# Connectors_GPIOs_old.net
KiCad netlist of a schematic drawn in Altium Designer
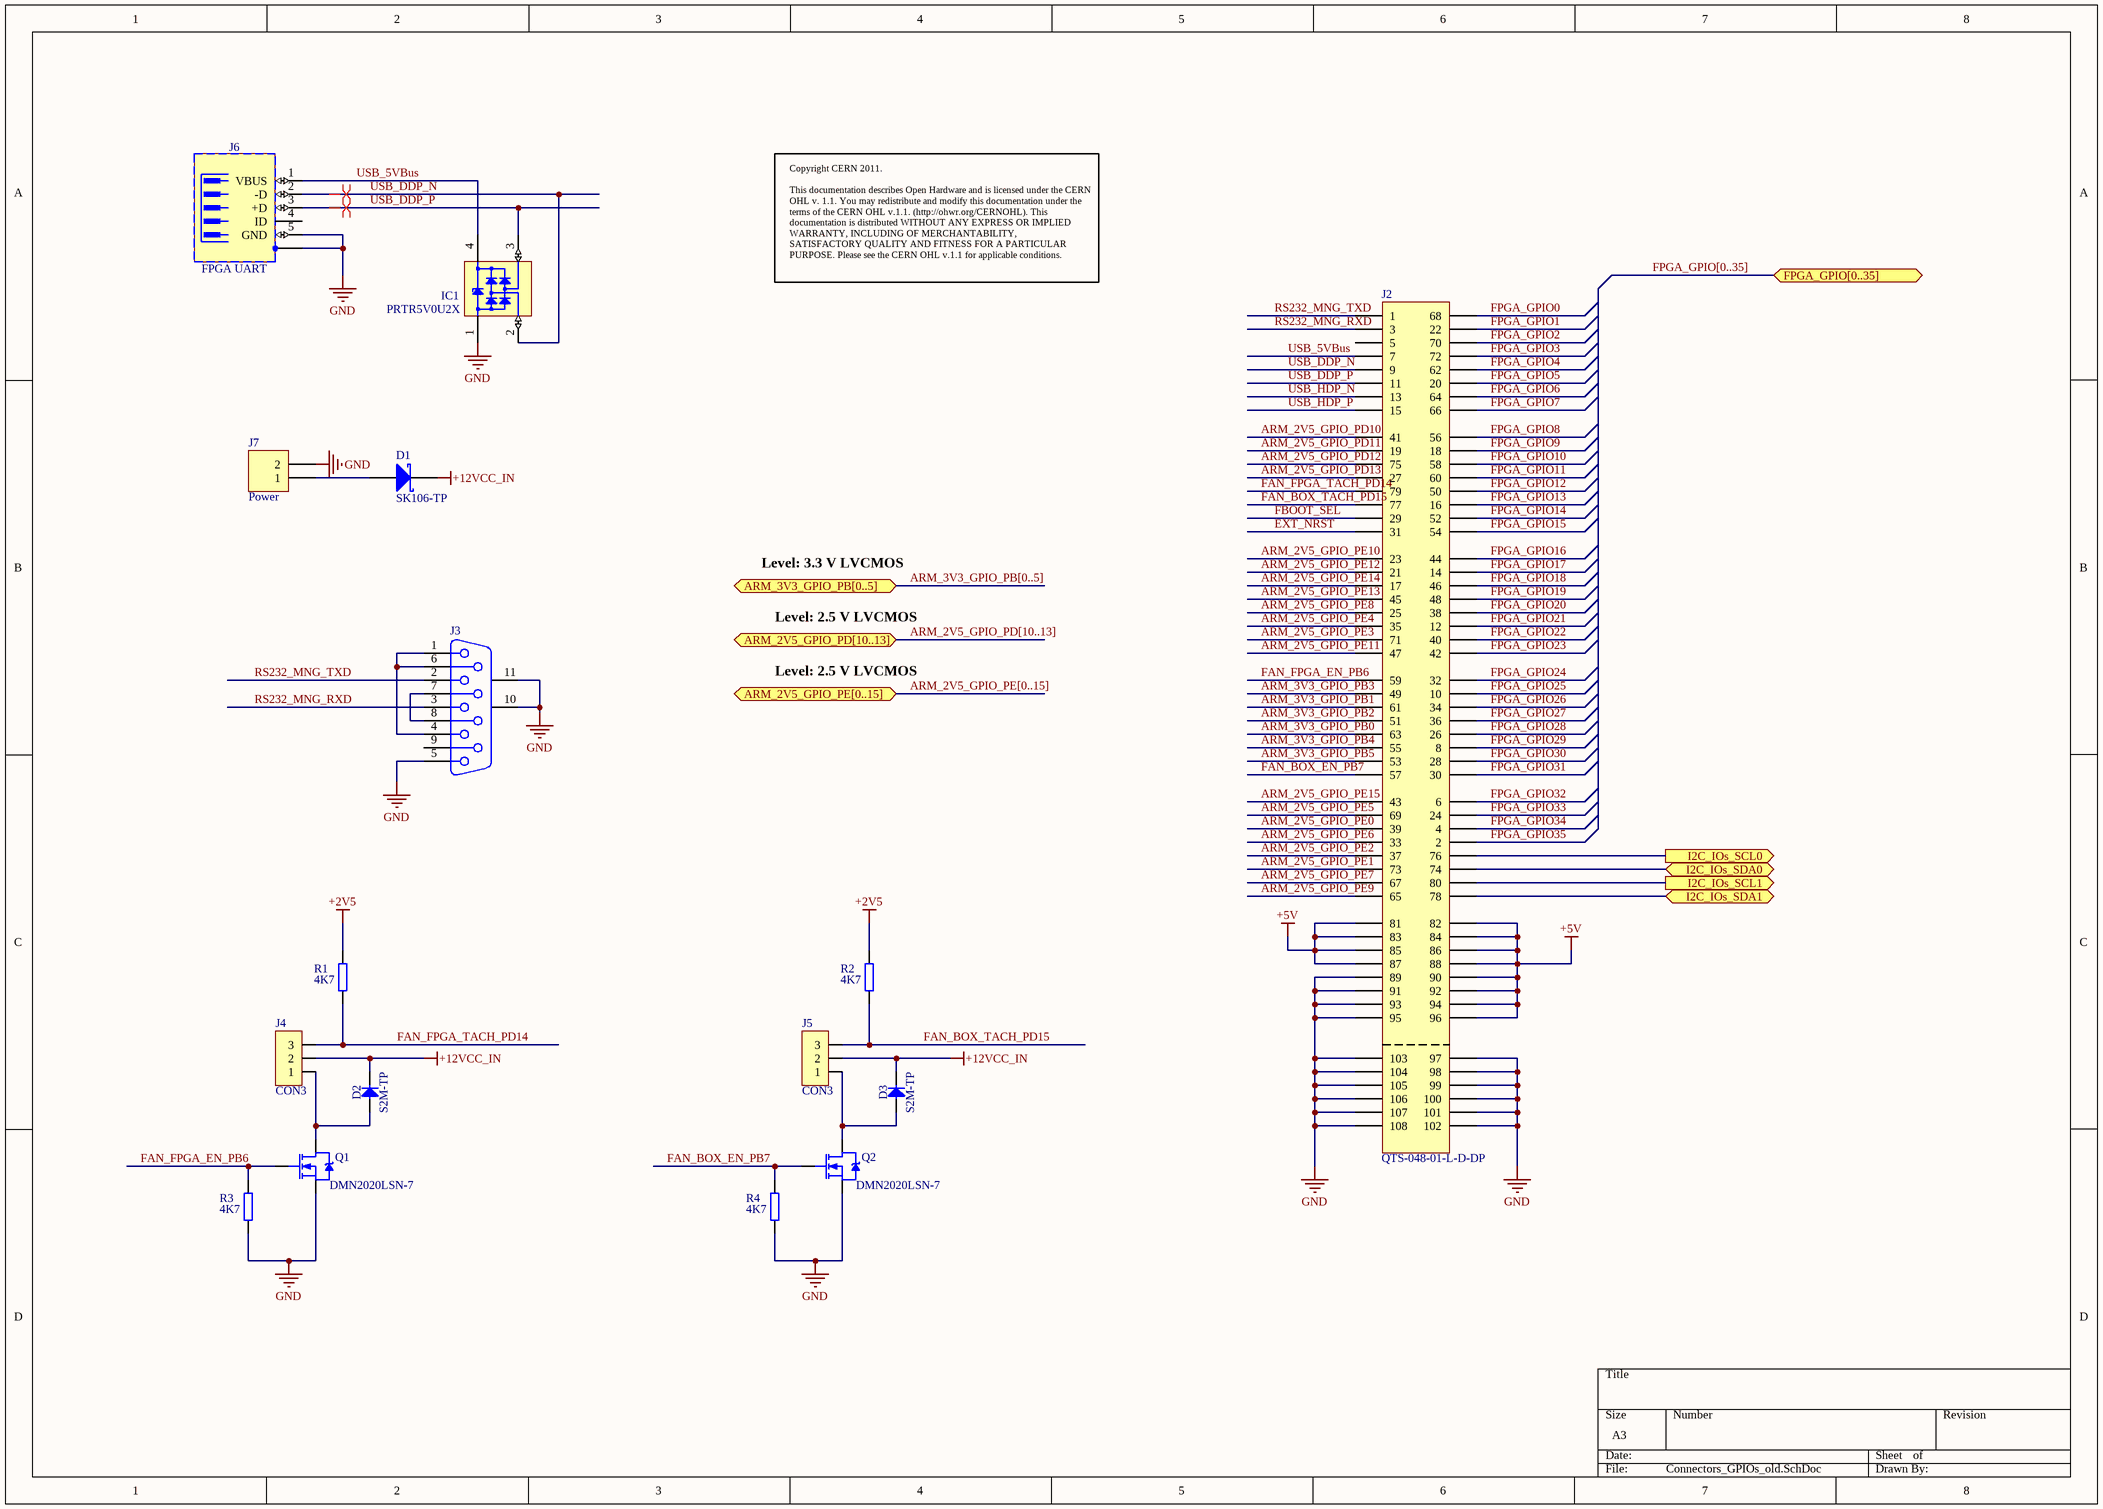
[diagram p0: Connectors_GPIOs_old.SchDoc]

(export (version "E")
  (design (tool "Eeschema 10.0.6"))
  (components
    (comp (ref "D1")
      (value "SK106-TP")
      (footprint "7S_WR:DO-214AB/SMB-MCC")
      (description "Schottky Diode 10A 60V")
      (libsource (lib "wr_switch") (part "SK106-TP"))
    )
    (comp (ref "D2")
      (value "S2M-TP")
      (footprint "DO-214AA/SMB-MCC")
      (description "2 A Silicon Rectifier 50 to 1000 Volts")
      (fields (field (name "AUTHOR") "CERN DEM JLC"))
      (libsource (lib "wr_switch") (part "S2M-TP"))
    )
    (comp (ref "D3")
      (value "S2M-TP")
      (footprint "DO-214AA/SMB-MCC")
      (description "2 A Silicon Rectifier 50 to 1000 Volts")
      (fields (field (name "AUTHOR") "CERN DEM JLC"))
      (libsource (lib "wr_switch") (part "S2M-TP"))
    )
    (comp (ref "IC1")
      (value "PRTR5V0U2X")
      (footprint "7S_WR:SOT190P230X110-4N")
      (description "Ultra Low Capacitance Double Rail-to-Rail ESD Protection Diode")
      (fields
        (field (name "VOLTAGE") "5.5V")
        (field (name "MANUFACTURER") "PHILIPS NXP")
        (field (name "AUTHOR") "CERN DEM JLC")
      )
      (libsource (lib "wr_switch") (part "PRTR5V0U2X"))
    )
    (comp (ref "J2")
      (value "QTS-048-01-L-D-DP")
      (footprint "7S_WR:QTS-048-XX-X-D-DP-A")
      (description "High Speed Ground Plane Header")
      (libsource (lib "wr_switch") (part "QTS-048-01-L-D-DP"))
    )
    (comp (ref "J3")
      (value "D Connector 9")
      (footprint "7S_WR:DSUB1.385-2H9")
      (description "Receptacle Assembly, 9 Position, Right Angle")
      (fields (field (name "PUBLISHER") "Altium Limited"))
      (libsource (lib "Miscellaneous Connectors") (part "D Connector 9"))
    )
    (comp (ref "J4")
      (value "CON3")
      (footprint "7S_WR:MOLEX_22-11-2032")
      (description "Connector")
      (libsource (lib "LIBRARY_SCH") (part "CON3"))
    )
    (comp (ref "J5")
      (value "CON3")
      (footprint "7S_WR:MOLEX_22-11-2032")
      (description "Connector")
      (libsource (lib "LIBRARY_SCH") (part "CON3"))
    )
    (comp (ref "J6")
      (value "FPGA UART")
      (footprint "7S_WR:TYCO_1734035-1")
      (description "5 Pin + 1 Shield USB Receptacle")
      (fields
        (field (name "PART NUMBER") "TYCO_1734035-1")
        (field (name "MANUFACTURER") "TYCO ELECTRONICS")
        (field (name "AUTHOR") "CERN DEM JLC")
      )
      (libsource (lib "Connectors") (part "Connector USB 5 Pin + 1Shield"))
    )
    (comp (ref "J7")
      (value "Power")
      (footprint "7S_WR:TYCO_794120_1")
      (description "Header, 2-Pin")
      (fields (field (name "PUBLISHER") "Altium Limited"))
      (libsource (lib "Miscellaneous Connectors") (part "Header 2"))
    )
    (comp (ref "Q1")
      (value "DMN2020LSN-7")
      (footprint "7S_WR:SC-59-3")
      (description "N-Channel Power MOSFET")
      (fields (field (name "MANUFACTURER") "Diodes Inc.") (field (name "PUBLISHER") "Altium Limited"))
      (libsource (lib "wr_switch") (part "NMOS-2"))
    )
    (comp (ref "Q2")
      (value "DMN2020LSN-7")
      (footprint "7S_WR:SC-59-3")
      (description "N-Channel Power MOSFET")
      (fields (field (name "MANUFACTURER") "Diodes Inc.") (field (name "PUBLISHER") "Altium Limited"))
      (libsource (lib "wr_switch") (part "NMOS-2"))
    )
    (comp (ref "R1")
      (value "4K7")
      (footprint "0603")
      (description "SMD Resistor")
      (fields (field (name "TOLERANCE") "±1%"))
      (libsource (lib "wr_switch") (part "RES_SMD"))
    )
    (comp (ref "R2")
      (value "4K7")
      (footprint "0603")
      (description "SMD Resistor")
      (fields (field (name "TOLERANCE") "±1%"))
      (libsource (lib "wr_switch") (part "RES_SMD"))
    )
    (comp (ref "R3")
      (value "4K7")
      (footprint "0603")
      (description "SMD Resistor")
      (fields (field (name "TOLERANCE") "±1%"))
      (libsource (lib "wr_switch") (part "RES_SMD"))
    )
    (comp (ref "R4")
      (value "4K7")
      (footprint "0603")
      (description "SMD Resistor")
      (fields (field (name "TOLERANCE") "±1%"))
      (libsource (lib "wr_switch") (part "RES_SMD"))
    )
  )
  (nets
    (net (code "1") (name "+2V5") (class "Default")
      (node (ref "R1") (pin "1") (pinfunction "1_1") (pintype "passive"))
      (node (ref "R2") (pin "1") (pinfunction "1_1") (pintype "passive"))
    )
    (net (code "2") (name "+5V") (class "Default")
      (node (ref "J2") (pin "81") (pinfunction "81_81") (pintype "passive"))
      (node (ref "J2") (pin "82") (pinfunction "82_82") (pintype "passive"))
      (node (ref "J2") (pin "83") (pinfunction "83_83") (pintype "passive"))
      (node (ref "J2") (pin "84") (pinfunction "84_84") (pintype "passive"))
      (node (ref "J2") (pin "85") (pinfunction "85_85") (pintype "passive"))
      (node (ref "J2") (pin "86") (pinfunction "86_86") (pintype "passive"))
      (node (ref "J2") (pin "87") (pinfunction "87_87") (pintype "passive"))
      (node (ref "J2") (pin "88") (pinfunction "88_88") (pintype "passive"))
      (node (ref "J2") (pin "90") (pinfunction "90_90") (pintype "passive"))
      (node (ref "J2") (pin "92") (pinfunction "92_92") (pintype "passive"))
      (node (ref "J2") (pin "94") (pinfunction "94_94") (pintype "passive"))
      (node (ref "J2") (pin "96") (pinfunction "96_96") (pintype "passive"))
    )
    (net (code "3") (name "+12VCC_IN") (class "Default")
      (node (ref "D1") (pin "1") (pinfunction "K_1") (pintype "passive"))
      (node (ref "D2") (pin "1") (pinfunction "C_1") (pintype "passive"))
      (node (ref "D3") (pin "1") (pinfunction "C_1") (pintype "passive"))
      (node (ref "J4") (pin "2") (pinfunction "2_2") (pintype "passive"))
      (node (ref "J5") (pin "2") (pinfunction "2_2") (pintype "passive"))
    )
    (net (code "4") (name "/ARM_2V5_GPIO_PD10") (class "Default")
      (node (ref "J2") (pin "41") (pinfunction "41_41") (pintype "passive"))
    )
    (net (code "5") (name "/ARM_2V5_GPIO_PD11") (class "Default")
      (node (ref "J2") (pin "19") (pinfunction "19_19") (pintype "passive"))
    )
    (net (code "6") (name "/ARM_2V5_GPIO_PD12") (class "Default")
      (node (ref "J2") (pin "75") (pinfunction "75_75") (pintype "passive"))
    )
    (net (code "7") (name "/ARM_2V5_GPIO_PD13") (class "Default")
      (node (ref "J2") (pin "27") (pinfunction "27_27") (pintype "passive"))
    )
    (net (code "9") (name "/ARM_2V5_GPIO_PE0") (class "Default")
      (node (ref "J2") (pin "39") (pinfunction "39_39") (pintype "passive"))
    )
    (net (code "10") (name "/ARM_2V5_GPIO_PE1") (class "Default")
      (node (ref "J2") (pin "73") (pinfunction "73_73") (pintype "passive"))
    )
    (net (code "11") (name "/ARM_2V5_GPIO_PE2") (class "Default")
      (node (ref "J2") (pin "37") (pinfunction "37_37") (pintype "passive"))
    )
    (net (code "12") (name "/ARM_2V5_GPIO_PE3") (class "Default")
      (node (ref "J2") (pin "71") (pinfunction "71_71") (pintype "passive"))
    )
    (net (code "13") (name "/ARM_2V5_GPIO_PE4") (class "Default")
      (node (ref "J2") (pin "35") (pinfunction "35_35") (pintype "passive"))
    )
    (net (code "14") (name "/ARM_2V5_GPIO_PE5") (class "Default")
      (node (ref "J2") (pin "69") (pinfunction "69_69") (pintype "passive"))
    )
    (net (code "15") (name "/ARM_2V5_GPIO_PE6") (class "Default")
      (node (ref "J2") (pin "33") (pinfunction "33_33") (pintype "passive"))
    )
    (net (code "16") (name "/ARM_2V5_GPIO_PE7") (class "Default")
      (node (ref "J2") (pin "67") (pinfunction "67_67") (pintype "passive"))
    )
    (net (code "17") (name "/ARM_2V5_GPIO_PE8") (class "Default")
      (node (ref "J2") (pin "25") (pinfunction "25_25") (pintype "passive"))
    )
    (net (code "18") (name "/ARM_2V5_GPIO_PE9") (class "Default")
      (node (ref "J2") (pin "65") (pinfunction "65_65") (pintype "passive"))
    )
    (net (code "19") (name "/ARM_2V5_GPIO_PE10") (class "Default")
      (node (ref "J2") (pin "23") (pinfunction "23_23") (pintype "passive"))
    )
    (net (code "20") (name "/ARM_2V5_GPIO_PE11") (class "Default")
      (node (ref "J2") (pin "47") (pinfunction "47_47") (pintype "passive"))
    )
    (net (code "21") (name "/ARM_2V5_GPIO_PE12") (class "Default")
      (node (ref "J2") (pin "21") (pinfunction "21_21") (pintype "passive"))
    )
    (net (code "22") (name "/ARM_2V5_GPIO_PE13") (class "Default")
      (node (ref "J2") (pin "45") (pinfunction "45_45") (pintype "passive"))
    )
    (net (code "23") (name "/ARM_2V5_GPIO_PE14") (class "Default")
      (node (ref "J2") (pin "17") (pinfunction "17_17") (pintype "passive"))
    )
    (net (code "24") (name "/ARM_2V5_GPIO_PE15") (class "Default")
      (node (ref "J2") (pin "43") (pinfunction "43_43") (pintype "passive"))
    )
    (net (code "26") (name "/ARM_3V3_GPIO_PB0") (class "Default")
      (node (ref "J2") (pin "63") (pinfunction "63_63") (pintype "passive"))
    )
    (net (code "27") (name "/ARM_3V3_GPIO_PB1") (class "Default")
      (node (ref "J2") (pin "61") (pinfunction "61_61") (pintype "passive"))
    )
    (net (code "28") (name "/ARM_3V3_GPIO_PB2") (class "Default")
      (node (ref "J2") (pin "51") (pinfunction "51_51") (pintype "passive"))
    )
    (net (code "29") (name "/ARM_3V3_GPIO_PB3") (class "Default")
      (node (ref "J2") (pin "49") (pinfunction "49_49") (pintype "passive"))
    )
    (net (code "30") (name "/ARM_3V3_GPIO_PB4") (class "Default")
      (node (ref "J2") (pin "55") (pinfunction "55_55") (pintype "passive"))
    )
    (net (code "31") (name "/ARM_3V3_GPIO_PB5") (class "Default")
      (node (ref "J2") (pin "53") (pinfunction "53_53") (pintype "passive"))
    )
    (net (code "33") (name "/EXT_NRST") (class "Default")
      (node (ref "J2") (pin "31") (pinfunction "31_31") (pintype "passive"))
    )
    (net (code "34") (name "/FAN_BOX_EN_PB7") (class "Default")
      (node (ref "J2") (pin "57") (pinfunction "57_57") (pintype "passive"))
      (node (ref "Q2") (pin "1") (pinfunction "G_1") (pintype "passive"))
      (node (ref "R4") (pin "1") (pinfunction "1_1") (pintype "passive"))
    )
    (net (code "35") (name "/FAN_BOX_TACH_PD15") (class "Default")
      (node (ref "J2") (pin "77") (pinfunction "77_77") (pintype "passive"))
      (node (ref "J5") (pin "3") (pinfunction "3_3") (pintype "passive"))
      (node (ref "R2") (pin "2") (pinfunction "2_2") (pintype "passive"))
    )
    (net (code "36") (name "/FAN_FPGA_EN_PB6") (class "Default")
      (node (ref "J2") (pin "59") (pinfunction "59_59") (pintype "passive"))
      (node (ref "Q1") (pin "1") (pinfunction "G_1") (pintype "passive"))
      (node (ref "R3") (pin "1") (pinfunction "1_1") (pintype "passive"))
    )
    (net (code "37") (name "/FAN_FPGA_TACH_PD14") (class "Default")
      (node (ref "J2") (pin "79") (pinfunction "79_79") (pintype "passive"))
      (node (ref "J4") (pin "3") (pinfunction "3_3") (pintype "passive"))
      (node (ref "R1") (pin "2") (pinfunction "2_2") (pintype "passive"))
    )
    (net (code "38") (name "/FBOOT_SEL") (class "Default")
      (node (ref "J2") (pin "29") (pinfunction "29_29") (pintype "passive"))
    )
    (net (code "39") (name "/FPGA_GPIO0") (class "Default")
      (node (ref "J2") (pin "68") (pinfunction "68_68") (pintype "passive"))
    )
    (net (code "40") (name "/FPGA_GPIO1") (class "Default")
      (node (ref "J2") (pin "22") (pinfunction "22_22") (pintype "passive"))
    )
    (net (code "41") (name "/FPGA_GPIO2") (class "Default")
      (node (ref "J2") (pin "70") (pinfunction "70_70") (pintype "passive"))
    )
    (net (code "42") (name "/FPGA_GPIO3") (class "Default")
      (node (ref "J2") (pin "72") (pinfunction "72_72") (pintype "passive"))
    )
    (net (code "43") (name "/FPGA_GPIO4") (class "Default")
      (node (ref "J2") (pin "62") (pinfunction "62_62") (pintype "passive"))
    )
    (net (code "44") (name "/FPGA_GPIO5") (class "Default")
      (node (ref "J2") (pin "20") (pinfunction "20_20") (pintype "passive"))
    )
    (net (code "45") (name "/FPGA_GPIO6") (class "Default")
      (node (ref "J2") (pin "64") (pinfunction "64_64") (pintype "passive"))
    )
    (net (code "46") (name "/FPGA_GPIO7") (class "Default")
      (node (ref "J2") (pin "66") (pinfunction "66_66") (pintype "passive"))
    )
    (net (code "47") (name "/FPGA_GPIO8") (class "Default")
      (node (ref "J2") (pin "56") (pinfunction "56_56") (pintype "passive"))
    )
    (net (code "48") (name "/FPGA_GPIO9") (class "Default")
      (node (ref "J2") (pin "18") (pinfunction "18_18") (pintype "passive"))
    )
    (net (code "49") (name "/FPGA_GPIO10") (class "Default")
      (node (ref "J2") (pin "58") (pinfunction "58_58") (pintype "passive"))
    )
    (net (code "50") (name "/FPGA_GPIO11") (class "Default")
      (node (ref "J2") (pin "60") (pinfunction "60_60") (pintype "passive"))
    )
    (net (code "51") (name "/FPGA_GPIO12") (class "Default")
      (node (ref "J2") (pin "50") (pinfunction "50_50") (pintype "passive"))
    )
    (net (code "52") (name "/FPGA_GPIO13") (class "Default")
      (node (ref "J2") (pin "16") (pinfunction "16_16") (pintype "passive"))
    )
    (net (code "53") (name "/FPGA_GPIO14") (class "Default")
      (node (ref "J2") (pin "52") (pinfunction "52_52") (pintype "passive"))
    )
    (net (code "54") (name "/FPGA_GPIO15") (class "Default")
      (node (ref "J2") (pin "54") (pinfunction "54_54") (pintype "passive"))
    )
    (net (code "55") (name "/FPGA_GPIO16") (class "Default")
      (node (ref "J2") (pin "44") (pinfunction "44_44") (pintype "passive"))
    )
    (net (code "56") (name "/FPGA_GPIO17") (class "Default")
      (node (ref "J2") (pin "14") (pinfunction "14_14") (pintype "passive"))
    )
    (net (code "57") (name "/FPGA_GPIO18") (class "Default")
      (node (ref "J2") (pin "46") (pinfunction "46_46") (pintype "passive"))
    )
    (net (code "58") (name "/FPGA_GPIO19") (class "Default")
      (node (ref "J2") (pin "48") (pinfunction "48_48") (pintype "passive"))
    )
    (net (code "59") (name "/FPGA_GPIO20") (class "Default")
      (node (ref "J2") (pin "38") (pinfunction "38_38") (pintype "passive"))
    )
    (net (code "60") (name "/FPGA_GPIO21") (class "Default")
      (node (ref "J2") (pin "12") (pinfunction "12_12") (pintype "passive"))
    )
    (net (code "61") (name "/FPGA_GPIO22") (class "Default")
      (node (ref "J2") (pin "40") (pinfunction "40_40") (pintype "passive"))
    )
    (net (code "62") (name "/FPGA_GPIO23") (class "Default")
      (node (ref "J2") (pin "42") (pinfunction "42_42") (pintype "passive"))
    )
    (net (code "63") (name "/FPGA_GPIO24") (class "Default")
      (node (ref "J2") (pin "32") (pinfunction "32_32") (pintype "passive"))
    )
    (net (code "64") (name "/FPGA_GPIO25") (class "Default")
      (node (ref "J2") (pin "10") (pinfunction "10_10") (pintype "passive"))
    )
    (net (code "65") (name "/FPGA_GPIO26") (class "Default")
      (node (ref "J2") (pin "34") (pinfunction "34_34") (pintype "passive"))
    )
    (net (code "66") (name "/FPGA_GPIO27") (class "Default")
      (node (ref "J2") (pin "36") (pinfunction "36_36") (pintype "passive"))
    )
    (net (code "67") (name "/FPGA_GPIO28") (class "Default")
      (node (ref "J2") (pin "26") (pinfunction "26_26") (pintype "passive"))
    )
    (net (code "68") (name "/FPGA_GPIO29") (class "Default")
      (node (ref "J2") (pin "8") (pinfunction "8_8") (pintype "passive"))
    )
    (net (code "69") (name "/FPGA_GPIO30") (class "Default")
      (node (ref "J2") (pin "28") (pinfunction "28_28") (pintype "passive"))
    )
    (net (code "70") (name "/FPGA_GPIO31") (class "Default")
      (node (ref "J2") (pin "30") (pinfunction "30_30") (pintype "passive"))
    )
    (net (code "71") (name "/FPGA_GPIO32") (class "Default")
      (node (ref "J2") (pin "6") (pinfunction "6_6") (pintype "passive"))
    )
    (net (code "72") (name "/FPGA_GPIO33") (class "Default")
      (node (ref "J2") (pin "24") (pinfunction "24_24") (pintype "passive"))
    )
    (net (code "73") (name "/FPGA_GPIO34") (class "Default")
      (node (ref "J2") (pin "4") (pinfunction "4_4") (pintype "passive"))
    )
    (net (code "74") (name "/FPGA_GPIO35") (class "Default")
      (node (ref "J2") (pin "2") (pinfunction "2_2") (pintype "passive"))
    )
    (net (code "76") (name "/I2C_IOs_SCL0") (class "Default")
      (node (ref "J2") (pin "76") (pinfunction "76_76") (pintype "passive"))
    )
    (net (code "77") (name "/I2C_IOs_SCL1") (class "Default")
      (node (ref "J2") (pin "80") (pinfunction "80_80") (pintype "passive"))
    )
    (net (code "78") (name "/I2C_IOs_SDA0") (class "Default")
      (node (ref "J2") (pin "74") (pinfunction "74_74") (pintype "passive"))
    )
    (net (code "79") (name "/I2C_IOs_SDA1") (class "Default")
      (node (ref "J2") (pin "78") (pinfunction "78_78") (pintype "passive"))
    )
    (net (code "80") (name "/RS232_MNG_RXD") (class "Default")
      (node (ref "J2") (pin "3") (pinfunction "3_3") (pintype "passive"))
      (node (ref "J3") (pin "3") (pinfunction "3_3") (pintype "passive"))
    )
    (net (code "81") (name "/RS232_MNG_TXD") (class "Default")
      (node (ref "J2") (pin "1") (pinfunction "1_1") (pintype "passive"))
      (node (ref "J3") (pin "2") (pinfunction "2_2") (pintype "passive"))
    )
    (net (code "82") (name "/USB_5VBus") (class "Default")
      (node (ref "IC1") (pin "4") (pinfunction "VCC_4") (pintype "power_in"))
      (node (ref "J2") (pin "7") (pinfunction "7_7") (pintype "passive"))
      (node (ref "J6") (pin "1") (pinfunction "VBUS_1") (pintype "bidirectional"))
    )
    (net (code "83") (name "/USB_DDP_N") (class "Default")
      (node (ref "IC1") (pin "2") (pinfunction "I/O1_2") (pintype "bidirectional"))
      (node (ref "J2") (pin "9") (pinfunction "9_9") (pintype "passive"))
      (node (ref "J6") (pin "2") (pinfunction "-D_2") (pintype "bidirectional"))
    )
    (net (code "84") (name "/USB_DDP_P") (class "Default")
      (node (ref "IC1") (pin "3") (pinfunction "I/O2_3") (pintype "bidirectional"))
      (node (ref "J2") (pin "11") (pinfunction "11_11") (pintype "passive"))
      (node (ref "J6") (pin "3") (pinfunction "+D_3") (pintype "bidirectional"))
    )
    (net (code "85") (name "/USB_HDP_N") (class "Default")
      (node (ref "J2") (pin "13") (pinfunction "13_13") (pintype "passive"))
    )
    (net (code "86") (name "/USB_HDP_P") (class "Default")
      (node (ref "J2") (pin "15") (pinfunction "15_15") (pintype "passive"))
    )
    (net (code "87") (name "GND") (class "Default")
      (node (ref "IC1") (pin "1") (pinfunction "GND_1") (pintype "power_in"))
      (node (ref "J2") (pin "100") (pinfunction "100_100") (pintype "passive"))
      (node (ref "J2") (pin "101") (pinfunction "101_101") (pintype "passive"))
      (node (ref "J2") (pin "102") (pinfunction "102_102") (pintype "passive"))
      (node (ref "J2") (pin "103") (pinfunction "103_103") (pintype "passive"))
      (node (ref "J2") (pin "104") (pinfunction "104_104") (pintype "passive"))
      (node (ref "J2") (pin "105") (pinfunction "105_105") (pintype "passive"))
      (node (ref "J2") (pin "106") (pinfunction "106_106") (pintype "passive"))
      (node (ref "J2") (pin "107") (pinfunction "107_107") (pintype "passive"))
      (node (ref "J2") (pin "108") (pinfunction "108_108") (pintype "passive"))
      (node (ref "J2") (pin "89") (pinfunction "89_89") (pintype "passive"))
      (node (ref "J2") (pin "91") (pinfunction "91_91") (pintype "passive"))
      (node (ref "J2") (pin "93") (pinfunction "93_93") (pintype "passive"))
      (node (ref "J2") (pin "95") (pinfunction "95_95") (pintype "passive"))
      (node (ref "J2") (pin "97") (pinfunction "97_97") (pintype "passive"))
      (node (ref "J2") (pin "98") (pinfunction "98_98") (pintype "passive"))
      (node (ref "J2") (pin "99") (pinfunction "99_99") (pintype "passive"))
      (node (ref "J3") (pin "10") (pinfunction "MH1_10") (pintype "passive"))
      (node (ref "J3") (pin "11") (pinfunction "MH2_11") (pintype "passive"))
      (node (ref "J3") (pin "5") (pinfunction "5_5") (pintype "passive"))
      (node (ref "J6") (pin "5") (pinfunction "GND_5") (pintype "bidirectional"))
      (node (ref "J6") (pin "6") (pinfunction "SH_6") (pintype "power_in"))
      (node (ref "J7") (pin "2") (pinfunction "2_2") (pintype "passive"))
      (node (ref "Q1") (pin "3") (pinfunction "S_3") (pintype "passive"))
      (node (ref "Q2") (pin "3") (pinfunction "S_3") (pintype "passive"))
      (node (ref "R3") (pin "2") (pinfunction "2_2") (pintype "passive"))
      (node (ref "R4") (pin "2") (pinfunction "2_2") (pintype "passive"))
    )
    (net (code "88") (name "Net-(D1-A)") (class "Default")
      (node (ref "D1") (pin "2") (pinfunction "A_2") (pintype "passive"))
      (node (ref "J7") (pin "1") (pinfunction "1_1") (pintype "passive"))
    )
    (net (code "89") (name "Net-(D2-A)") (class "Default")
      (node (ref "D2") (pin "2") (pinfunction "A_2") (pintype "passive"))
      (node (ref "J4") (pin "1") (pinfunction "1_1") (pintype "passive"))
      (node (ref "Q1") (pin "2") (pinfunction "D_2") (pintype "passive"))
    )
    (net (code "90") (name "Net-(D3-A)") (class "Default")
      (node (ref "D3") (pin "2") (pinfunction "A_2") (pintype "passive"))
      (node (ref "J5") (pin "1") (pinfunction "1_1") (pintype "passive"))
      (node (ref "Q2") (pin "2") (pinfunction "D_2") (pintype "passive"))
    )
    (net (code "91") (name "Net-(J3-Pad1)") (class "Default")
      (node (ref "J3") (pin "1") (pinfunction "1_1") (pintype "passive"))
      (node (ref "J3") (pin "4") (pinfunction "4_4") (pintype "passive"))
      (node (ref "J3") (pin "6") (pinfunction "6_6") (pintype "passive"))
    )
    (net (code "92") (name "Net-(J3-Pad7)") (class "Default")
      (node (ref "J3") (pin "7") (pinfunction "7_7") (pintype "passive"))
      (node (ref "J3") (pin "8") (pinfunction "8_8") (pintype "passive"))
    )
    (net (code "93") (name "unconnected-(J2-Pad5)") (class "Default")
      (node (ref "J2") (pin "5") (pinfunction "5_5") (pintype "passive"))
    )
    (net (code "94") (name "unconnected-(J3-Pad9)") (class "Default")
      (node (ref "J3") (pin "9") (pinfunction "9_9") (pintype "passive"))
    )
    (net (code "95") (name "unconnected-(J6-ID-Pad4)") (class "Default")
      (node (ref "J6") (pin "4") (pinfunction "ID_4") (pintype "passive"))
    )
  )
)
